# Complete.net
KiCad netlist of a schematic drawn in Altium Designer
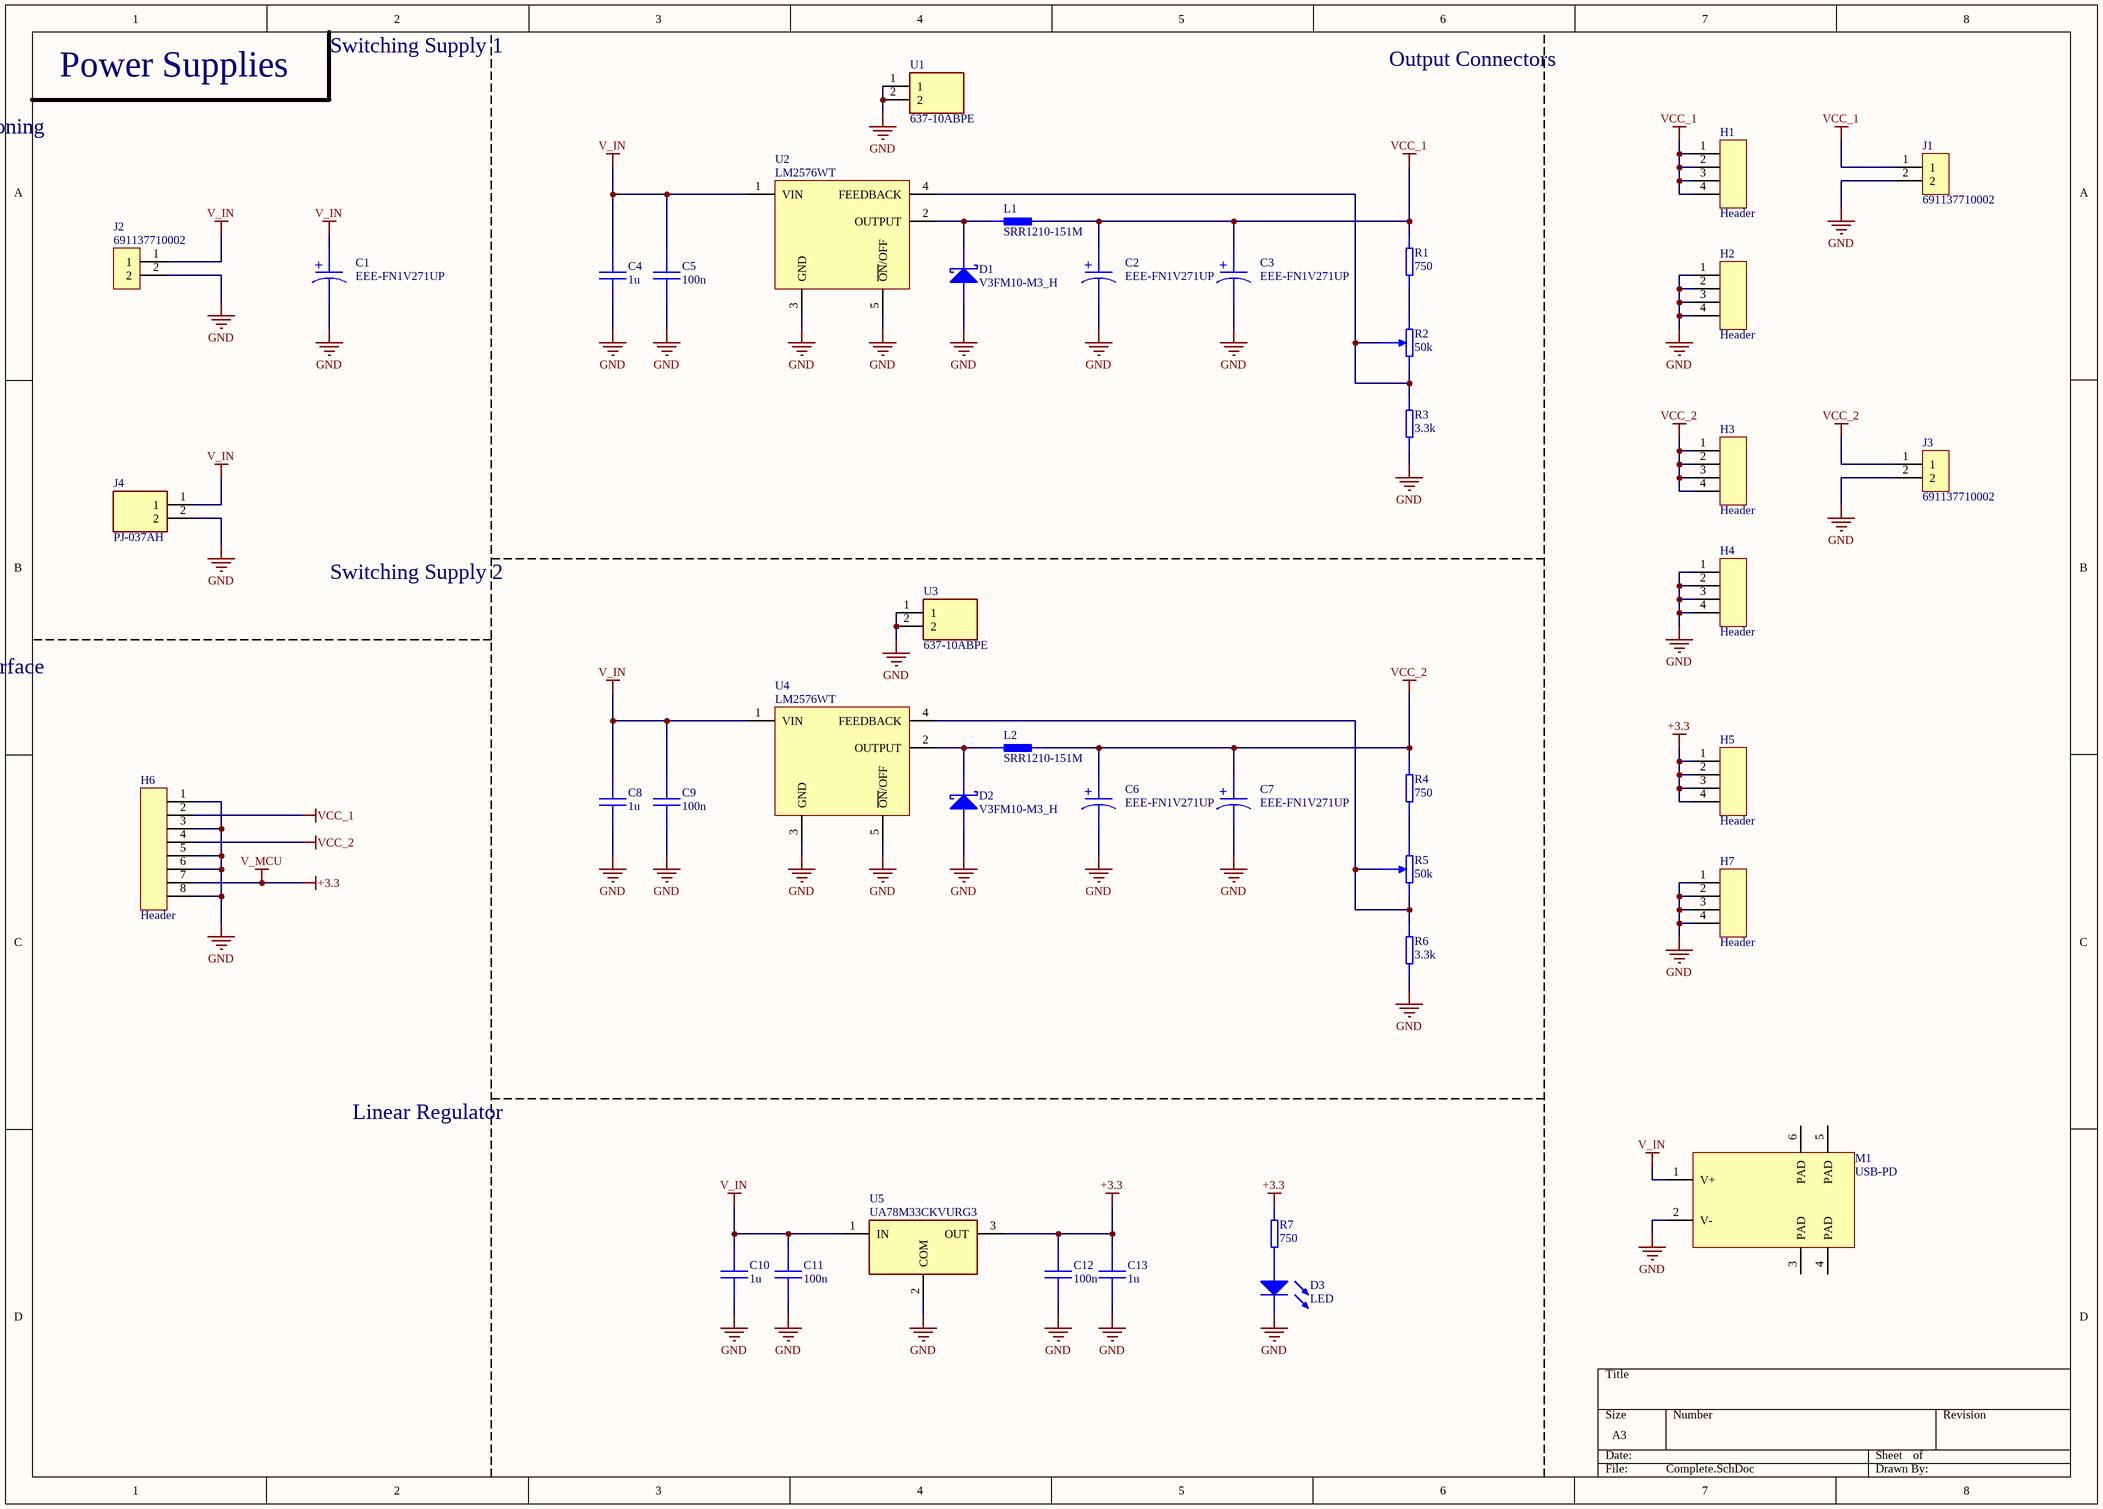
[diagram p0: Complete.SchDoc]

(export (version "E")
  (design (tool "Eeschema 10.0.6"))
  (components
    (comp (ref "C1")
      (value "EEE-FN1V271UP")
      (footprint "EEHZT1E331UP")
      (description "Capacitor Polarised")
      (fields (field (name "MOUSER PART NUMBER") "667-EEE-FN1V271UP"))
      (libsource (lib "TD") (part "EEE-FN1V271UP"))
    )
    (comp (ref "C2")
      (value "EEE-FN1V271UP")
      (footprint "EEHZT1E331UP")
      (description "Capacitor Polarised")
      (fields (field (name "MOUSER PART NUMBER") "667-EEE-FN1V271UP"))
      (libsource (lib "TD") (part "EEE-FN1V271UP"))
    )
    (comp (ref "C3")
      (value "EEE-FN1V271UP")
      (footprint "EEHZT1E331UP")
      (description "Capacitor Polarised")
      (fields (field (name "MOUSER PART NUMBER") "667-EEE-FN1V271UP"))
      (libsource (lib "TD") (part "EEE-FN1V271UP"))
    )
    (comp (ref "C4")
      (value "1u")
      (footprint "CAP0805")
      (description "Non Polarized Capacitor")
      (libsource (lib "TD") (part "Capacitor - Non Polarized"))
    )
    (comp (ref "C5")
      (value "100n")
      (footprint "CAP0805")
      (description "Non Polarized Capacitor")
      (libsource (lib "TD") (part "Capacitor - Non Polarized"))
    )
    (comp (ref "C6")
      (value "EEE-FN1V271UP")
      (footprint "EEHZT1E331UP")
      (description "Capacitor Polarised")
      (fields (field (name "MOUSER PART NUMBER") "667-EEE-FN1V271UP"))
      (libsource (lib "TD") (part "EEE-FN1V271UP"))
    )
    (comp (ref "C7")
      (value "EEE-FN1V271UP")
      (footprint "EEHZT1E331UP")
      (description "Capacitor Polarised")
      (fields (field (name "MOUSER PART NUMBER") "667-EEE-FN1V271UP"))
      (libsource (lib "TD") (part "EEE-FN1V271UP"))
    )
    (comp (ref "C8")
      (value "1u")
      (footprint "CAP0805")
      (description "Non Polarized Capacitor")
      (libsource (lib "TD") (part "Capacitor - Non Polarized"))
    )
    (comp (ref "C9")
      (value "100n")
      (footprint "CAP0805")
      (description "Non Polarized Capacitor")
      (libsource (lib "TD") (part "Capacitor - Non Polarized"))
    )
    (comp (ref "C10")
      (value "1u")
      (footprint "CAP0805")
      (description "Non Polarized Capacitor")
      (libsource (lib "TD") (part "Capacitor - Non Polarized"))
    )
    (comp (ref "C11")
      (value "100n")
      (footprint "CAP0805")
      (description "Non Polarized Capacitor")
      (libsource (lib "TD") (part "Capacitor - Non Polarized"))
    )
    (comp (ref "C12")
      (value "100n")
      (footprint "CAP0805")
      (description "Non Polarized Capacitor")
      (libsource (lib "TD") (part "Capacitor - Non Polarized"))
    )
    (comp (ref "C13")
      (value "1u")
      (footprint "CAP0805")
      (description "Non Polarized Capacitor")
      (libsource (lib "TD") (part "Capacitor - Non Polarized"))
    )
    (comp (ref "D1")
      (value "V3FM10-M3_H")
      (footprint "DO-219AB")
      (description "Schottky Diode")
      (fields
        (field (name "MANUFACTURER_PART_NUMBER") "V3FM10-M3/H")
        (field (name "MOUSER PART NUMBER") "78-V3FM10-M3/H")
      )
      (libsource (lib "TD") (part "V3FM10-M3_H"))
    )
    (comp (ref "D2")
      (value "V3FM10-M3_H")
      (footprint "DO-219AB")
      (description "Schottky Diode")
      (fields
        (field (name "MANUFACTURER_PART_NUMBER") "V3FM10-M3/H")
        (field (name "MOUSER PART NUMBER") "78-V3FM10-M3/H")
      )
      (libsource (lib "TD") (part "V3FM10-M3_H"))
    )
    (comp (ref "D3")
      (value "LED")
      (footprint "LEDM2012X80N")
      (description "General Purpose LED")
      (libsource (lib "TD") (part "LED"))
    )
    (comp (ref "H1")
      (value "Header")
      (footprint "IEEE_Workshop_FP:Header_1X4")
      (description "4-Pin Header")
      (libsource (lib "TD") (part "4-Pin Header"))
    )
    (comp (ref "H2")
      (value "Header")
      (footprint "IEEE_Workshop_FP:Header_1X4")
      (description "4-Pin Header")
      (libsource (lib "TD") (part "4-Pin Header"))
    )
    (comp (ref "H3")
      (value "Header")
      (footprint "IEEE_Workshop_FP:Header_1X4")
      (description "4-Pin Header")
      (libsource (lib "TD") (part "4-Pin Header"))
    )
    (comp (ref "H4")
      (value "Header")
      (footprint "IEEE_Workshop_FP:Header_1X4")
      (description "4-Pin Header")
      (libsource (lib "TD") (part "4-Pin Header"))
    )
    (comp (ref "H5")
      (value "Header")
      (footprint "IEEE_Workshop_FP:Header_1X4")
      (description "4-Pin Header")
      (libsource (lib "TD") (part "4-Pin Header"))
    )
    (comp (ref "H6")
      (value "Header")
      (footprint "Header_1X8")
      (description "8-Pin Header")
      (libsource (lib "TD") (part "8-Pin Header"))
    )
    (comp (ref "H7")
      (value "Header")
      (footprint "IEEE_Workshop_FP:Header_1X4")
      (description "4-Pin Header")
      (libsource (lib "TD") (part "4-Pin Header"))
    )
    (comp (ref "J1")
      (value "691137710002")
      (footprint "SHDR2W70P0X500_1X2_1000X750X1160P")
      (description "Connector")
      (fields (field (name "MOUSER PART NUMBER") "710-691137710002"))
      (libsource (lib "TD") (part "691137710002"))
    )
    (comp (ref "J2")
      (value "691137710002")
      (footprint "SHDR2W70P0X500_1X2_1000X750X1160P")
      (description "Connector")
      (fields (field (name "MOUSER PART NUMBER") "710-691137710002"))
      (libsource (lib "") (part "691137710002_1"))
    )
    (comp (ref "J3")
      (value "691137710002")
      (footprint "SHDR2W70P0X500_1X2_1000X750X1160P")
      (description "Connector")
      (fields (field (name "MOUSER PART NUMBER") "710-691137710002"))
      (libsource (lib "TD") (part "691137710002"))
    )
    (comp (ref "J4")
      (value "PJ-037AH")
      (footprint "PJ037AH")
      (description "Connector")
      (fields (field (name "MOUSER PART NUMBER") "490-PJ-037AH"))
      (libsource (lib "TD") (part "PJ-037AH"))
    )
    (comp (ref "L1")
      (value "SRR1210-151M")
      (footprint "INDPM120120X1000N-D")
      (description "Inductor")
      (fields (field (name "MOUSER PART NUMBER") "652-SRR1210-151M"))
      (libsource (lib "TD") (part "SRR1210-151M"))
    )
    (comp (ref "L2")
      (value "SRR1210-151M")
      (footprint "INDPM120120X1000N-D")
      (description "Inductor")
      (fields (field (name "MOUSER PART NUMBER") "652-SRR1210-151M"))
      (libsource (lib "TD") (part "SRR1210-151M"))
    )
    (comp (ref "M1")
      (value "USB-PD")
      (footprint "USB_C-PD")
      (libsource (lib "IEEE_Workshop_SCH") (part "USB-PD"))
    )
    (comp (ref "R1")
      (value "750")
      (footprint "RESC0805")
      (description "Resistor")
      (libsource (lib "TD") (part "Resistor"))
    )
    (comp (ref "R2")
      (value "50k")
      (footprint "3339P1103LF")
      (description "Potentionmeter")
      (libsource (lib "TD") (part "Potentiometer"))
    )
    (comp (ref "R3")
      (value "3.3k")
      (footprint "RESC0805")
      (description "Resistor")
      (libsource (lib "TD") (part "Resistor"))
    )
    (comp (ref "R4")
      (value "750")
      (footprint "RESC0805")
      (description "Resistor")
      (libsource (lib "TD") (part "Resistor"))
    )
    (comp (ref "R5")
      (value "50k")
      (footprint "3339P1103LF")
      (description "Potentionmeter")
      (libsource (lib "TD") (part "Potentiometer"))
    )
    (comp (ref "R6")
      (value "3.3k")
      (footprint "RESC0805")
      (description "Resistor")
      (libsource (lib "TD") (part "Resistor"))
    )
    (comp (ref "R7")
      (value "750")
      (footprint "RESC0805")
      (description "Resistor")
      (libsource (lib "TD") (part "Resistor"))
    )
    (comp (ref "U1")
      (value "637-10ABPE")
      (footprint "SamacSys:63710ABPE")
      (description "Undefined or Miscellaneous")
      (fields (field (name "MOUSER PART NUMBER") "567-637-10ABPE"))
      (libsource (lib "*") (part "637-10ABPE"))
    )
    (comp (ref "U2")
      (value "LM2576WT")
      (footprint "TO-220-5")
      (description "Integrated Circuit")
      (fields
        (field (name "MANUFACTURER_PART_NUMBER") "LM2576WU-TR")
        (field (name "MOUSER PART NUMBER") "998-LM2576WT")
      )
      (libsource (lib "TD") (part "LM2576WT"))
    )
    (comp (ref "U3")
      (value "637-10ABPE")
      (footprint "SamacSys:63710ABPE")
      (description "Undefined or Miscellaneous")
      (fields (field (name "MOUSER PART NUMBER") "567-637-10ABPE"))
      (libsource (lib "*") (part "637-10ABPE"))
    )
    (comp (ref "U4")
      (value "LM2576WT")
      (footprint "IEEE_Workshop_FP:TO-220-5")
      (description "Integrated Circuit")
      (fields
        (field (name "MANUFACTURER_PART_NUMBER") "LM2576WU-TR")
        (field (name "MOUSER PART NUMBER") "998-LM2576WT")
      )
      (libsource (lib "TD") (part "LM2576WT"))
    )
    (comp (ref "U5")
      (value "UA78M33CKVURG3")
      (footprint "TO-252-3")
      (description "Linear Voltage Regulator")
      (fields (field (name "MOUSER PART NUMBER") "595-UA78M33CKVURG3"))
      (libsource (lib "TD") (part "UA78M33CKVURG3"))
    )
  )
  (nets
    (net (code "1") (name "+3.3") (class "Default")
      (node (ref "C12") (pin "1") (pintype "passive"))
      (node (ref "C13") (pin "1") (pintype "passive"))
      (node (ref "H5") (pin "1") (pintype "passive"))
      (node (ref "H5") (pin "2") (pintype "passive"))
      (node (ref "H5") (pin "3") (pintype "passive"))
      (node (ref "H5") (pin "4") (pintype "passive"))
      (node (ref "H6") (pin "7") (pintype "passive"))
      (node (ref "R7") (pin "1") (pintype "passive"))
      (node (ref "U5") (pin "3") (pinfunction "OUT_3") (pintype "passive"))
    )
    (net (code "2") (name "GND") (class "Default")
      (node (ref "C1") (pin "2") (pintype "passive"))
      (node (ref "C10") (pin "2") (pintype "passive"))
      (node (ref "C11") (pin "2") (pintype "passive"))
      (node (ref "C12") (pin "2") (pintype "passive"))
      (node (ref "C13") (pin "2") (pintype "passive"))
      (node (ref "C2") (pin "2") (pintype "passive"))
      (node (ref "C3") (pin "2") (pintype "passive"))
      (node (ref "C4") (pin "2") (pintype "passive"))
      (node (ref "C5") (pin "2") (pintype "passive"))
      (node (ref "C6") (pin "2") (pintype "passive"))
      (node (ref "C7") (pin "2") (pintype "passive"))
      (node (ref "C8") (pin "2") (pintype "passive"))
      (node (ref "C9") (pin "2") (pintype "passive"))
      (node (ref "D1") (pin "2") (pinfunction "A_2") (pintype "passive"))
      (node (ref "D2") (pin "2") (pinfunction "A_2") (pintype "passive"))
      (node (ref "D3") (pin "1") (pinfunction "K_1") (pintype "passive"))
      (node (ref "H2") (pin "1") (pintype "passive"))
      (node (ref "H2") (pin "2") (pintype "passive"))
      (node (ref "H2") (pin "3") (pintype "passive"))
      (node (ref "H2") (pin "4") (pintype "passive"))
      (node (ref "H4") (pin "1") (pintype "passive"))
      (node (ref "H4") (pin "2") (pintype "passive"))
      (node (ref "H4") (pin "3") (pintype "passive"))
      (node (ref "H4") (pin "4") (pintype "passive"))
      (node (ref "H6") (pin "1") (pintype "passive"))
      (node (ref "H6") (pin "3") (pintype "passive"))
      (node (ref "H6") (pin "5") (pintype "passive"))
      (node (ref "H6") (pin "6") (pintype "passive"))
      (node (ref "H6") (pin "8") (pintype "passive"))
      (node (ref "H7") (pin "1") (pintype "passive"))
      (node (ref "H7") (pin "2") (pintype "passive"))
      (node (ref "H7") (pin "3") (pintype "passive"))
      (node (ref "H7") (pin "4") (pintype "passive"))
      (node (ref "J1") (pin "2") (pinfunction "2_2") (pintype "passive"))
      (node (ref "J2") (pin "2") (pinfunction "2_2") (pintype "passive"))
      (node (ref "J3") (pin "2") (pinfunction "2_2") (pintype "passive"))
      (node (ref "J4") (pin "2") (pinfunction "2_2") (pintype "passive"))
      (node (ref "M1") (pin "2") (pinfunction "V-_2") (pintype "passive"))
      (node (ref "R3") (pin "2") (pintype "passive"))
      (node (ref "R6") (pin "2") (pintype "passive"))
      (node (ref "U1") (pin "1") (pinfunction "1_1") (pintype "passive"))
      (node (ref "U1") (pin "2") (pinfunction "2_2") (pintype "passive"))
      (node (ref "U2") (pin "3") (pinfunction "GND_3") (pintype "passive"))
      (node (ref "U2") (pin "5") (pinfunction "~{ON}/OFF_5") (pintype "passive"))
      (node (ref "U3") (pin "1") (pinfunction "1_1") (pintype "passive"))
      (node (ref "U3") (pin "2") (pinfunction "2_2") (pintype "passive"))
      (node (ref "U4") (pin "3") (pinfunction "GND_3") (pintype "passive"))
      (node (ref "U4") (pin "5") (pinfunction "~{ON}/OFF_5") (pintype "passive"))
      (node (ref "U5") (pin "2") (pinfunction "COM_2") (pintype "passive"))
    )
    (net (code "3") (name "Net-(D1-K)") (class "Default")
      (node (ref "D1") (pin "1") (pinfunction "K_1") (pintype "passive"))
      (node (ref "L1") (pin "1") (pintype "passive"))
      (node (ref "U2") (pin "2") (pinfunction "OUTPUT_2") (pintype "passive"))
    )
    (net (code "4") (name "Net-(D2-K)") (class "Default")
      (node (ref "D2") (pin "1") (pinfunction "K_1") (pintype "passive"))
      (node (ref "L2") (pin "1") (pintype "passive"))
      (node (ref "U4") (pin "2") (pinfunction "OUTPUT_2") (pintype "passive"))
    )
    (net (code "5") (name "Net-(D3-A)") (class "Default")
      (node (ref "D3") (pin "2") (pinfunction "A_2") (pintype "passive"))
      (node (ref "R7") (pin "2") (pintype "passive"))
    )
    (net (code "6") (name "Net-(R1-Pad2)") (class "Default")
      (node (ref "R1") (pin "2") (pintype "passive"))
      (node (ref "R2") (pin "1") (pintype "passive"))
    )
    (net (code "7") (name "Net-(R4-Pad2)") (class "Default")
      (node (ref "R4") (pin "2") (pintype "passive"))
      (node (ref "R5") (pin "1") (pintype "passive"))
    )
    (net (code "8") (name "Net-(U2-FEEDBACK)") (class "Default")
      (node (ref "R2") (pin "2") (pintype "passive"))
      (node (ref "R2") (pin "3") (pintype "passive"))
      (node (ref "R3") (pin "1") (pintype "passive"))
      (node (ref "U2") (pin "4") (pinfunction "FEEDBACK_4") (pintype "passive"))
    )
    (net (code "9") (name "Net-(U4-FEEDBACK)") (class "Default")
      (node (ref "R5") (pin "2") (pintype "passive"))
      (node (ref "R5") (pin "3") (pintype "passive"))
      (node (ref "R6") (pin "1") (pintype "passive"))
      (node (ref "U4") (pin "4") (pinfunction "FEEDBACK_4") (pintype "passive"))
    )
    (net (code "10") (name "VCC_1") (class "Default")
      (node (ref "C2") (pin "1") (pintype "passive"))
      (node (ref "C3") (pin "1") (pintype "passive"))
      (node (ref "H1") (pin "1") (pintype "passive"))
      (node (ref "H1") (pin "2") (pintype "passive"))
      (node (ref "H1") (pin "3") (pintype "passive"))
      (node (ref "H1") (pin "4") (pintype "passive"))
      (node (ref "H6") (pin "2") (pintype "passive"))
      (node (ref "J1") (pin "1") (pinfunction "1_1") (pintype "passive"))
      (node (ref "L1") (pin "2") (pintype "passive"))
      (node (ref "R1") (pin "1") (pintype "passive"))
    )
    (net (code "11") (name "VCC_2") (class "Default")
      (node (ref "C6") (pin "1") (pintype "passive"))
      (node (ref "C7") (pin "1") (pintype "passive"))
      (node (ref "H3") (pin "1") (pintype "passive"))
      (node (ref "H3") (pin "2") (pintype "passive"))
      (node (ref "H3") (pin "3") (pintype "passive"))
      (node (ref "H3") (pin "4") (pintype "passive"))
      (node (ref "H6") (pin "4") (pintype "passive"))
      (node (ref "J3") (pin "1") (pinfunction "1_1") (pintype "passive"))
      (node (ref "L2") (pin "2") (pintype "passive"))
      (node (ref "R4") (pin "1") (pintype "passive"))
    )
    (net (code "12") (name "V_IN") (class "Default")
      (node (ref "C1") (pin "1") (pintype "passive"))
      (node (ref "C10") (pin "1") (pintype "passive"))
      (node (ref "C11") (pin "1") (pintype "passive"))
      (node (ref "C4") (pin "1") (pintype "passive"))
      (node (ref "C5") (pin "1") (pintype "passive"))
      (node (ref "C8") (pin "1") (pintype "passive"))
      (node (ref "C9") (pin "1") (pintype "passive"))
      (node (ref "J2") (pin "1") (pinfunction "1_1") (pintype "passive"))
      (node (ref "J4") (pin "1") (pinfunction "1_1") (pintype "passive"))
      (node (ref "M1") (pin "1") (pinfunction "V+_1") (pintype "passive"))
      (node (ref "U2") (pin "1") (pinfunction "VIN_1") (pintype "passive"))
      (node (ref "U4") (pin "1") (pinfunction "VIN_1") (pintype "passive"))
      (node (ref "U5") (pin "1") (pinfunction "IN_1") (pintype "passive"))
    )
    (net (code "13") (name "unconnected-(M1-PAD-Pad3)") (class "Default")
      (node (ref "M1") (pin "3") (pinfunction "PAD_3") (pintype "passive"))
    )
    (net (code "14") (name "unconnected-(M1-PAD-Pad4)") (class "Default")
      (node (ref "M1") (pin "4") (pinfunction "PAD_4") (pintype "passive"))
    )
    (net (code "15") (name "unconnected-(M1-PAD-Pad5)") (class "Default")
      (node (ref "M1") (pin "5") (pinfunction "PAD_5") (pintype "passive"))
    )
    (net (code "16") (name "unconnected-(M1-PAD-Pad6)") (class "Default")
      (node (ref "M1") (pin "6") (pinfunction "PAD_6") (pintype "passive"))
    )
  )
)
